# SCR.net
KiCad netlist of a schematic drawn in Altium Designer
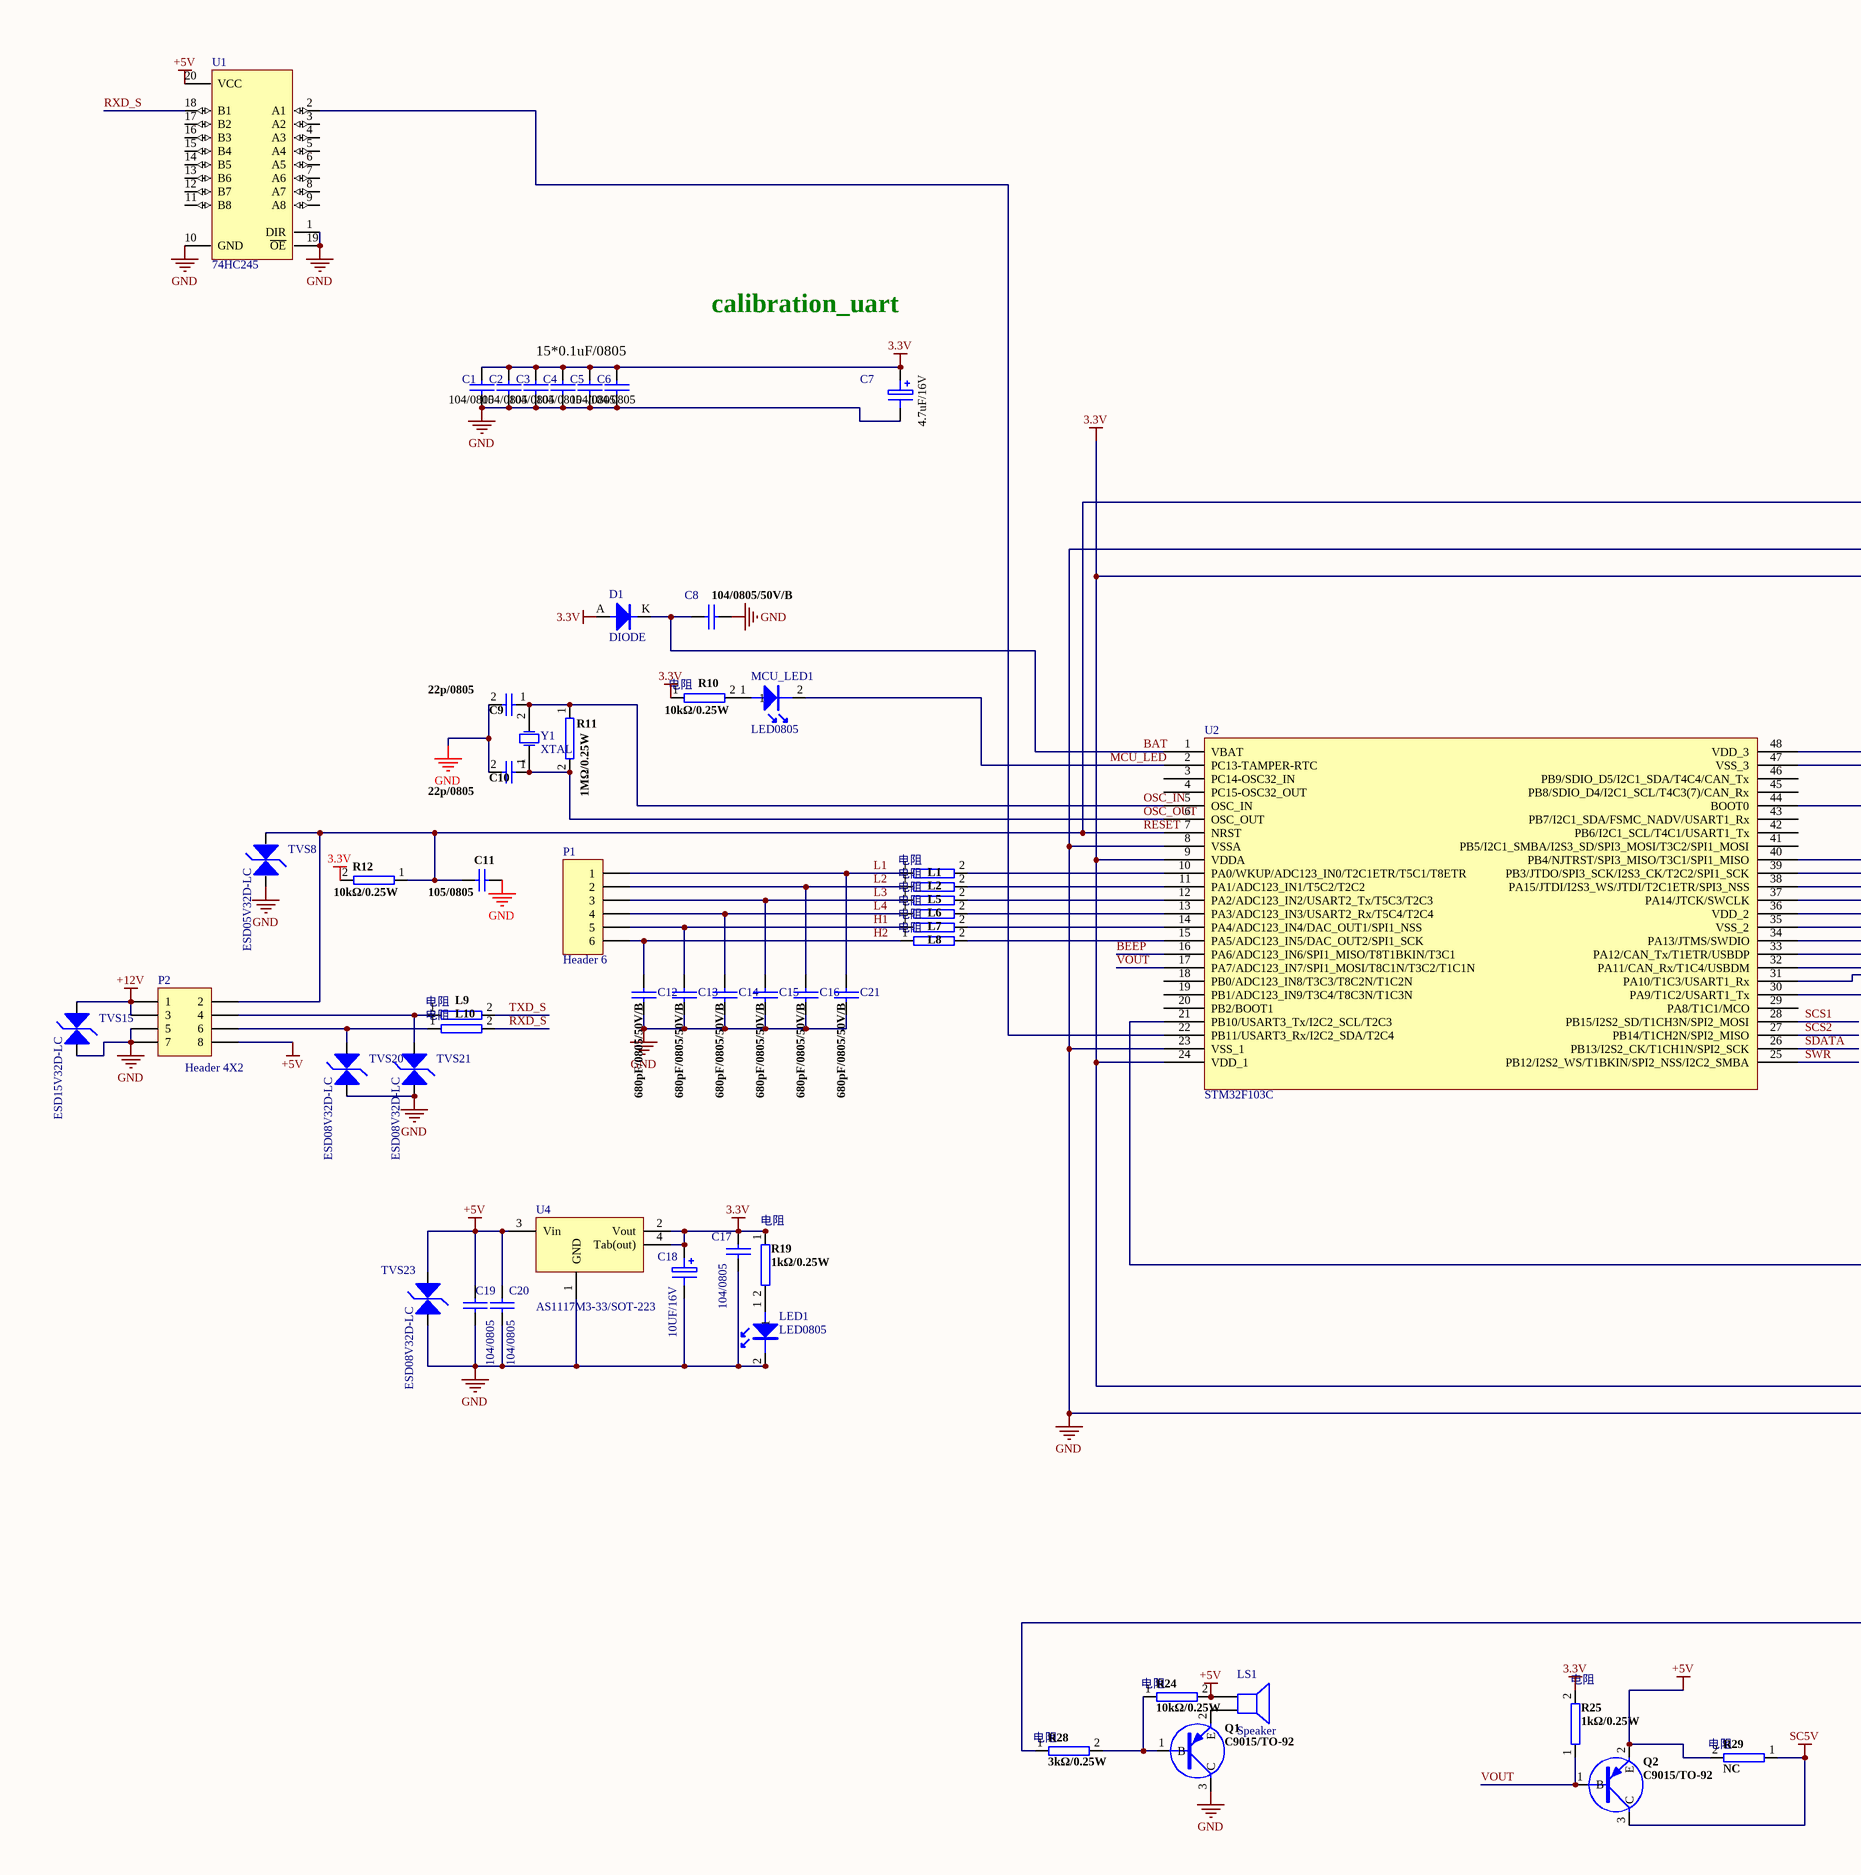
[diagram p0: SCR.SchDoc, left]
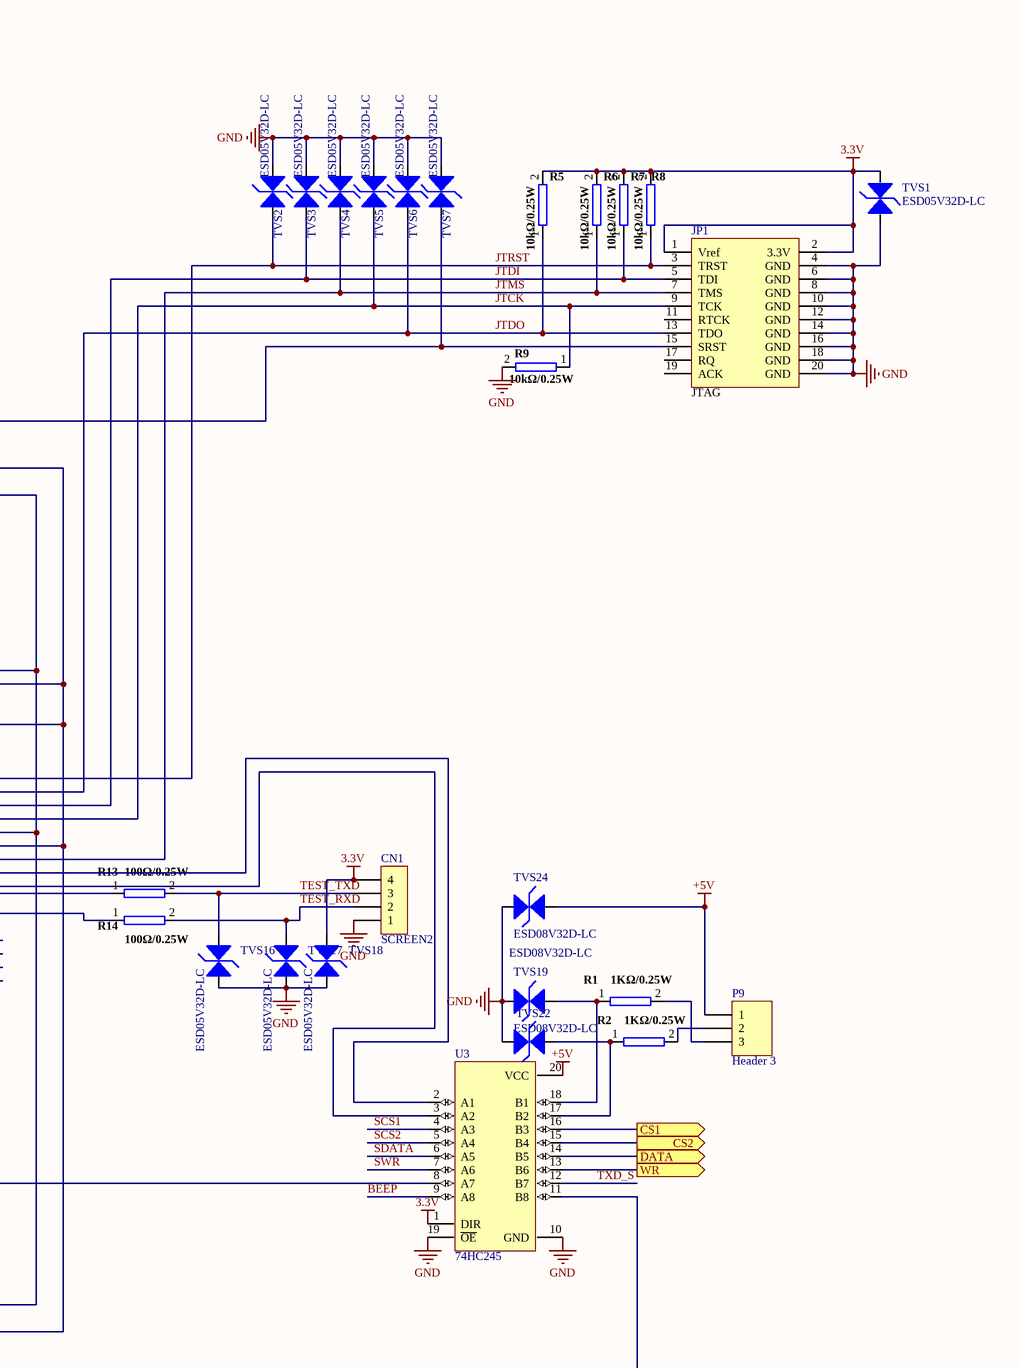
[diagram p1: SCR.SchDoc, right]

(export (version "E")
  (design (tool "Eeschema 10.0.6"))
  (components
    (comp (ref "C1")
      (value "104/0805")
      (footprint "COOLCONTROL:C0805")
      (description "Capacitor")
      (libsource (lib "*") (part "CAP"))
    )
    (comp (ref "C2")
      (value "104/0805")
      (footprint "C0805")
      (description "Capacitor")
      (libsource (lib "*") (part "CAP"))
    )
    (comp (ref "C3")
      (value "104/0805")
      (footprint "C0805")
      (description "Capacitor")
      (libsource (lib "*") (part "CAP"))
    )
    (comp (ref "C4")
      (value "104/0805")
      (footprint "C0805")
      (description "Capacitor")
      (libsource (lib "*") (part "CAP"))
    )
    (comp (ref "C5")
      (value "104/0805")
      (footprint "C0805")
      (description "Capacitor")
      (libsource (lib "*") (part "CAP"))
    )
    (comp (ref "C6")
      (value "104/0805")
      (footprint "C0805")
      (description "Capacitor")
      (libsource (lib "*") (part "CAP"))
    )
    (comp (ref "C7")
      (value "4.7uF/16V")
      (footprint "CAP5X5")
      (description "Electrolytic Capacitor")
      (libsource (lib "*") (part "ELECTRO1"))
    )
    (comp (ref "C8")
      (value "104/0805/50V/B")
      (footprint "C0805")
      (description "Capacitor")
      (fields (field (name "Comment") "104/0805"))
      (libsource (lib "*") (part "CAP"))
    )
    (comp (ref "C9") (value "22p/0805") (footprint "C0805") (libsource (lib "") (part "CAP_2")))
    (comp (ref "C10") (value "22p/0805") (footprint "C0805") (libsource (lib "") (part "CAP_2")))
    (comp (ref "C11")
      (value "105/0805")
      (footprint "C0805")
      (description "Capacitor")
      (fields (field (name "PUBLISHER") "Altium Limited"))
      (libsource (lib "") (part "CAP_1"))
    )
    (comp (ref "C12")
      (value "680pF/0805/50V/B")
      (footprint "C0805")
      (description "Capacitor")
      (fields (field (name "Comment") "104/0805"))
      (libsource (lib "*") (part "CAP"))
    )
    (comp (ref "C13")
      (value "680pF/0805/50V/B")
      (footprint "C0805")
      (description "Capacitor")
      (fields (field (name "Comment") "104/0805"))
      (libsource (lib "*") (part "CAP"))
    )
    (comp (ref "C14")
      (value "680pF/0805/50V/B")
      (footprint "C0805")
      (description "Capacitor")
      (fields (field (name "Comment") "104/0805"))
      (libsource (lib "*") (part "CAP"))
    )
    (comp (ref "C15")
      (value "680pF/0805/50V/B")
      (footprint "C0805")
      (description "Capacitor")
      (fields (field (name "Comment") "104/0805"))
      (libsource (lib "*") (part "CAP"))
    )
    (comp (ref "C16")
      (value "680pF/0805/50V/B")
      (footprint "C0805")
      (description "Capacitor")
      (fields (field (name "Comment") "104/0805"))
      (libsource (lib "*") (part "CAP"))
    )
    (comp (ref "C17")
      (value "104/0805")
      (footprint "C0805")
      (description "Capacitor")
      (libsource (lib "*") (part "CAP"))
    )
    (comp (ref "C18")
      (value "10UF/16V")
      (footprint "C3216")
      (description "Electrolytic Capacitor")
      (libsource (lib "*") (part "ELECTRO1"))
    )
    (comp (ref "C19")
      (value "104/0805")
      (footprint "C0805")
      (description "Capacitor")
      (libsource (lib "*") (part "CAP"))
    )
    (comp (ref "C20")
      (value "104/0805")
      (footprint "C0805")
      (description "Capacitor")
      (libsource (lib "*") (part "CAP"))
    )
    (comp (ref "C21")
      (value "680pF/0805/50V/B")
      (footprint "C0805")
      (description "Capacitor")
      (fields (field (name "Comment") "104/0805"))
      (libsource (lib "*") (part "CAP"))
    )
    (comp (ref "CN1")
      (value "SCREEN2")
      (footprint "COOLCONTROL:4Pin-2.54")
      (description "Connector")
      (libsource (lib "COOLCONTROL") (part "CON4"))
    )
    (comp (ref "D1") (value "DIODE") (footprint "SOD123") (libsource (lib "COOLCONTROL") (part "DIODE")))
    (comp (ref "JP1") (value "JTAG") (footprint "IDC20_A") (libsource (lib "COOLCONTROL") (part "JTAG20")))
    (comp (ref "L1") (value "FBMA-11-160808-601T") (footprint "R0805") (libsource (lib "*") (part "RES2")))
    (comp (ref "L2") (value "FBMA-11-160808-601T") (footprint "R0805") (libsource (lib "*") (part "RES2")))
    (comp (ref "L5") (value "FBMA-11-160808-601T") (footprint "R0805") (libsource (lib "*") (part "RES2")))
    (comp (ref "L6") (value "FBMA-11-160808-601T") (footprint "R0805") (libsource (lib "*") (part "RES2")))
    (comp (ref "L7") (value "FBMA-11-160808-601T") (footprint "R0805") (libsource (lib "*") (part "RES2")))
    (comp (ref "L8") (value "FBMA-11-160808-601T") (footprint "R0805") (libsource (lib "*") (part "RES2")))
    (comp (ref "L9") (value "FBMA-11-160808-601T") (footprint "R0805") (libsource (lib "*") (part "RES2")))
    (comp (ref "L10") (value "FBMA-11-160808-601T") (footprint "R0805") (libsource (lib "*") (part "RES2")))
    (comp (ref "LED1")
      (value "LED0805")
      (footprint "LED_0805")
      (libsource (lib "COOLCONTROL") (part "LED0805"))
    )
    (comp (ref "LS1")
      (value "Speaker")
      (footprint "Thermometer:SPK")
      (description "Loudspeaker")
      (fields (field (name "PUBLISHER") "Altium Limited"))
      (libsource (lib "Miscellaneous Devices") (part "Speaker"))
    )
    (comp (ref "MCU_LED1")
      (value "LED0805")
      (footprint "LED_0805")
      (libsource (lib "COOLCONTROL") (part "LED0805"))
    )
    (comp (ref "P1")
      (value "Header 6")
      (footprint "HDR1X6")
      (description "Header, 6-Pin")
      (fields (field (name "PUBLISHER") "Altium Limited"))
      (libsource (lib "Miscellaneous Connectors") (part "Header 6"))
    )
    (comp (ref "P2")
      (value "Header 4X2")
      (footprint "pcb2D3D库0903:RJ45")
      (description "Header, 4-Pin, Dual row")
      (fields (field (name "PUBLISHER") "Altium Limited"))
      (libsource (lib "Miscellaneous Connectors") (part "Header 4X2"))
    )
    (comp (ref "P9")
      (value "Header 3")
      (footprint "HDR1X3")
      (description "Header, 3-Pin")
      (fields (field (name "PUBLISHER") "Altium Limited"))
      (libsource (lib "Miscellaneous Connectors") (part "Header 3"))
    )
    (comp (ref "Q1") (value "C9015/TO-92") (footprint "TO-92B") (libsource (lib "SCREEN") (part "PNP")))
    (comp (ref "Q2")
      (value "C9015/TO-92")
      (footprint "SOT-23 - 9015")
      (libsource (lib "SCREEN") (part "PNP"))
    )
    (comp (ref "R1") (value "1KΩ/0.25W") (footprint "COOLCONTROL:R0805") (libsource (lib "*") (part "RES2")))
    (comp (ref "R2") (value "1KΩ/0.25W") (footprint "COOLCONTROL:R0805") (libsource (lib "*") (part "RES2")))
    (comp (ref "R5") (value "10kΩ/0.25W") (footprint "R0805") (libsource (lib "") (part "RES2_1")))
    (comp (ref "R6") (value "10kΩ/0.25W") (footprint "R0805") (libsource (lib "") (part "RES2_1")))
    (comp (ref "R7") (value "10kΩ/0.25W") (footprint "R0805") (libsource (lib "") (part "RES2_1")))
    (comp (ref "R8") (value "10kΩ/0.25W") (footprint "R0805") (libsource (lib "") (part "RES2_1")))
    (comp (ref "R9") (value "10kΩ/0.25W") (footprint "R0805") (libsource (lib "") (part "RES2_1")))
    (comp (ref "R10") (value "10kΩ/0.25W") (footprint "R0805") (libsource (lib "*") (part "RES2")))
    (comp (ref "R11") (value "1MΩ/0.25W") (footprint "R0805") (libsource (lib "*") (part "RES2")))
    (comp (ref "R12") (value "10kΩ/0.25W") (footprint "R0805") (libsource (lib "*") (part "RES2")))
    (comp (ref "R13")
      (value "100Ω/0.25W")
      (footprint "COOLCONTROL:R0805")
      (libsource (lib "*") (part "RES2"))
    )
    (comp (ref "R14")
      (value "100Ω/0.25W")
      (footprint "COOLCONTROL:R0805")
      (libsource (lib "*") (part "RES2"))
    )
    (comp (ref "R19") (value "1kΩ/0.25W") (footprint "R0805") (libsource (lib "*") (part "RES2")))
    (comp (ref "R24") (value "10kΩ/0.25W") (footprint "R0805") (libsource (lib "*") (part "RES2")))
    (comp (ref "R25") (value "1kΩ/0.25W") (footprint "R0805") (libsource (lib "*") (part "RES2")))
    (comp (ref "R28") (value "3kΩ/0.25W") (footprint "R0805") (libsource (lib "*") (part "RES2")))
    (comp (ref "R29") (value "NC") (footprint "R0805") (libsource (lib "*") (part "RES2")))
    (comp (ref "TVS1")
      (value "ESD05V32D-LC")
      (footprint "SOD323")
      (libsource (lib "COOLCONTROL") (part "TVS"))
    )
    (comp (ref "TVS2")
      (value "ESD05V32D-LC")
      (footprint "SOD323")
      (libsource (lib "COOLCONTROL") (part "TVS"))
    )
    (comp (ref "TVS3")
      (value "ESD05V32D-LC")
      (footprint "SOD323")
      (libsource (lib "COOLCONTROL") (part "TVS"))
    )
    (comp (ref "TVS4")
      (value "ESD05V32D-LC")
      (footprint "SOD323")
      (libsource (lib "COOLCONTROL") (part "TVS"))
    )
    (comp (ref "TVS5")
      (value "ESD05V32D-LC")
      (footprint "SOD323")
      (libsource (lib "COOLCONTROL") (part "TVS"))
    )
    (comp (ref "TVS6")
      (value "ESD05V32D-LC")
      (footprint "SOD323")
      (libsource (lib "COOLCONTROL") (part "TVS"))
    )
    (comp (ref "TVS7")
      (value "ESD05V32D-LC")
      (footprint "SOD323")
      (libsource (lib "COOLCONTROL") (part "TVS"))
    )
    (comp (ref "TVS8")
      (value "ESD05V32D-LC")
      (footprint "SOD323")
      (libsource (lib "COOLCONTROL") (part "TVS"))
    )
    (comp (ref "TVS15")
      (value "ESD15V32D-LC")
      (footprint "SOD323")
      (libsource (lib "COOLCONTROL") (part "TVS"))
    )
    (comp (ref "TVS16")
      (value "ESD05V32D-LC")
      (footprint "SOD323")
      (libsource (lib "COOLCONTROL") (part "TVS"))
    )
    (comp (ref "TVS17")
      (value "ESD05V32D-LC")
      (footprint "SOD323")
      (libsource (lib "COOLCONTROL") (part "TVS"))
    )
    (comp (ref "TVS18")
      (value "ESD05V32D-LC")
      (footprint "SOD323")
      (libsource (lib "COOLCONTROL") (part "TVS"))
    )
    (comp (ref "TVS19")
      (value "ESD08V32D-LC")
      (footprint "SOD323")
      (libsource (lib "COOLCONTROL") (part "TVS"))
    )
    (comp (ref "TVS20")
      (value "ESD08V32D-LC")
      (footprint "SOD323")
      (libsource (lib "COOLCONTROL") (part "TVS"))
    )
    (comp (ref "TVS21")
      (value "ESD08V32D-LC")
      (footprint "SOD323")
      (libsource (lib "COOLCONTROL") (part "TVS"))
    )
    (comp (ref "TVS22")
      (value "ESD08V32D-LC")
      (footprint "SOD323")
      (libsource (lib "COOLCONTROL") (part "TVS"))
    )
    (comp (ref "TVS23")
      (value "ESD08V32D-LC")
      (footprint "SOD323")
      (libsource (lib "COOLCONTROL") (part "TVS"))
    )
    (comp (ref "TVS24")
      (value "ESD08V32D-LC")
      (footprint "SOD323")
      (libsource (lib "COOLCONTROL") (part "TVS"))
    )
    (comp (ref "U1")
      (value "74HC245")
      (footprint "JD1622(V3.0):SOP-20")
      (libsource (lib "") (part "74LS245_1"))
    )
    (comp (ref "U2")
      (value "STM32F103C")
      (footprint "Thermometer:LC-LQFP-48_7x7x05P")
      (description "STM32单片机48引脚")
      (libsource (lib "Thermometer") (part "STM32F103C"))
    )
    (comp (ref "U3")
      (value "74HC245")
      (footprint "JD1622(V3.0):SOP-20")
      (libsource (lib "制冷控制") (part "74LS245"))
    )
    (comp (ref "U4")
      (value "AS1117M3-33/SOT-223")
      (footprint "Thermometer:SOT-223-3L(M3)")
      (libsource (lib "COOLCONTROL") (part "AS1117M3-33"))
    )
    (comp (ref "Y1")
      (value "XTAL")
      (footprint "JD1622(V3.0):XTAL2")
      (description "Crystal Oscillator")
      (fields (field (name "PUBLISHER") "Altium Limited"))
      (libsource (lib "Miscellaneous Devices") (part "XTAL"))
    )
  )
  (nets
    (net (code "1") (name "+5V") (class "Default")
      (node (ref "C19") (pin "1") (pinfunction "1_1") (pintype "passive"))
      (node (ref "C20") (pin "1") (pinfunction "1_1") (pintype "passive"))
      (node (ref "LS1") (pin "1") (pinfunction "1_1") (pintype "passive"))
      (node (ref "P2") (pin "8") (pinfunction "8_8") (pintype "passive"))
      (node (ref "P9") (pin "1") (pinfunction "1_1") (pintype "passive"))
      (node (ref "Q2") (pin "2") (pinfunction "E_2") (pintype "passive"))
      (node (ref "R24") (pin "2") (pintype "passive"))
      (node (ref "R29") (pin "2") (pintype "passive"))
      (node (ref "TVS23") (pin "1") (pinfunction "1_1") (pintype "passive"))
      (node (ref "TVS24") (pin "1") (pinfunction "1_1") (pintype "passive"))
      (node (ref "U1") (pin "20") (pinfunction "VCC_20") (pintype "power_in"))
      (node (ref "U3") (pin "20") (pinfunction "VCC_20") (pintype "power_in"))
      (node (ref "U4") (pin "3") (pinfunction "Vin_3") (pintype "passive"))
    )
    (net (code "2") (name "+12V") (class "Default")
      (node (ref "P2") (pin "1") (pinfunction "1_1") (pintype "passive"))
      (node (ref "P2") (pin "3") (pinfunction "3_3") (pintype "passive"))
      (node (ref "TVS15") (pin "1") (pinfunction "1_1") (pintype "passive"))
    )
    (net (code "3") (name "/BAT") (class "Default")
      (node (ref "C8") (pin "1") (pinfunction "1_1") (pintype "passive"))
      (node (ref "D1") (pin "K") (pinfunction "K_K") (pintype "passive"))
      (node (ref "U2") (pin "1") (pinfunction "VBAT_1") (pintype "passive"))
    )
    (net (code "4") (name "/BEEP") (class "Default")
      (node (ref "U2") (pin "16") (pinfunction "PA6/ADC123_IN6/SPI1_MISO/T8T1BKIN/T3C1_16") (pintype "passive"))
      (node (ref "U3") (pin "9") (pinfunction "A8_9") (pintype "bidirectional"))
    )
    (net (code "5") (name "/CS1") (class "Default")
      (node (ref "U3") (pin "16") (pinfunction "B3_16") (pintype "bidirectional"))
    )
    (net (code "6") (name "/CS2") (class "Default")
      (node (ref "U3") (pin "15") (pinfunction "B4_15") (pintype "bidirectional"))
    )
    (net (code "7") (name "/DATA") (class "Default")
      (node (ref "U3") (pin "14") (pinfunction "B5_14") (pintype "bidirectional"))
    )
    (net (code "8") (name "/H1") (class "Default")
      (node (ref "C13") (pin "2") (pinfunction "2_2") (pintype "passive"))
      (node (ref "L7") (pin "1") (pintype "passive"))
      (node (ref "P1") (pin "5") (pinfunction "5_5") (pintype "passive"))
    )
    (net (code "9") (name "/H2") (class "Default")
      (node (ref "C12") (pin "2") (pinfunction "2_2") (pintype "passive"))
      (node (ref "L8") (pin "1") (pintype "passive"))
      (node (ref "P1") (pin "6") (pinfunction "6_6") (pintype "passive"))
    )
    (net (code "10") (name "/JTCK") (class "Default")
      (node (ref "JP1") (pin "9") (pinfunction "TCK_9") (pintype "passive"))
      (node (ref "R9") (pin "1") (pintype "passive"))
      (node (ref "TVS5") (pin "1") (pinfunction "1_1") (pintype "passive"))
      (node (ref "U2") (pin "37") (pinfunction "PA14/JTCK/SWCLK_37") (pintype "passive"))
    )
    (net (code "11") (name "/JTDI") (class "Default")
      (node (ref "JP1") (pin "5") (pinfunction "TDI_5") (pintype "passive"))
      (node (ref "R7") (pin "1") (pintype "passive"))
      (node (ref "TVS3") (pin "1") (pinfunction "1_1") (pintype "passive"))
      (node (ref "U2") (pin "38") (pinfunction "PA15/JTDI/I2S3_WS/JTDI/T2C1ETR/SPI3_NSS_38") (pintype "passive"))
    )
    (net (code "12") (name "/JTDO") (class "Default")
      (node (ref "JP1") (pin "13") (pinfunction "TDO_13") (pintype "passive"))
      (node (ref "R5") (pin "1") (pintype "passive"))
      (node (ref "TVS6") (pin "1") (pinfunction "1_1") (pintype "passive"))
      (node (ref "U2") (pin "39") (pinfunction "PB3/JTDO/SPI3_SCK/I2S3_CK/T2C2/SPI1_SCK_39") (pintype "passive"))
    )
    (net (code "13") (name "/JTMS") (class "Default")
      (node (ref "JP1") (pin "7") (pinfunction "TMS_7") (pintype "passive"))
      (node (ref "R6") (pin "1") (pintype "passive"))
      (node (ref "TVS4") (pin "1") (pinfunction "1_1") (pintype "passive"))
      (node (ref "U2") (pin "34") (pinfunction "PA13/JTMS/SWDIO_34") (pintype "passive"))
    )
    (net (code "14") (name "/JTRST") (class "Default")
      (node (ref "JP1") (pin "3") (pinfunction "TRST_3") (pintype "passive"))
      (node (ref "R8") (pin "1") (pintype "passive"))
      (node (ref "TVS2") (pin "1") (pinfunction "1_1") (pintype "passive"))
      (node (ref "U2") (pin "40") (pinfunction "PB4/NJTRST/SPI3_MISO/T3C1/SPI1_MISO_40") (pintype "passive"))
    )
    (net (code "15") (name "/L1") (class "Default")
      (node (ref "C21") (pin "2") (pinfunction "2_2") (pintype "passive"))
      (node (ref "L1") (pin "1") (pintype "passive"))
      (node (ref "P1") (pin "1") (pinfunction "1_1") (pintype "passive"))
    )
    (net (code "16") (name "/L2") (class "Default")
      (node (ref "C16") (pin "2") (pinfunction "2_2") (pintype "passive"))
      (node (ref "L2") (pin "1") (pintype "passive"))
      (node (ref "P1") (pin "2") (pinfunction "2_2") (pintype "passive"))
    )
    (net (code "17") (name "/L3") (class "Default")
      (node (ref "C15") (pin "2") (pinfunction "2_2") (pintype "passive"))
      (node (ref "L5") (pin "1") (pintype "passive"))
      (node (ref "P1") (pin "3") (pinfunction "3_3") (pintype "passive"))
    )
    (net (code "18") (name "/L4") (class "Default")
      (node (ref "C14") (pin "2") (pinfunction "2_2") (pintype "passive"))
      (node (ref "L6") (pin "1") (pintype "passive"))
      (node (ref "P1") (pin "4") (pinfunction "4_4") (pintype "passive"))
    )
    (net (code "19") (name "/MCU_LED") (class "Default")
      (node (ref "MCU_LED1") (pin "2") (pinfunction "2_2") (pintype "passive"))
      (node (ref "U2") (pin "2") (pinfunction "PC13-TAMPER-RTC_2") (pintype "passive"))
    )
    (net (code "20") (name "/OSC_IN") (class "Default")
      (node (ref "C9") (pin "1") (pintype "passive"))
      (node (ref "R11") (pin "1") (pintype "passive"))
      (node (ref "U2") (pin "5") (pinfunction "OSC_IN_5") (pintype "passive"))
      (node (ref "Y1") (pin "2") (pinfunction "OSC2_2") (pintype "passive"))
    )
    (net (code "21") (name "/OSC_OUT") (class "Default")
      (node (ref "C10") (pin "1") (pintype "passive"))
      (node (ref "R11") (pin "2") (pintype "passive"))
      (node (ref "U2") (pin "6") (pinfunction "OSC_OUT_6") (pintype "passive"))
      (node (ref "Y1") (pin "1") (pinfunction "OSC1_1") (pintype "passive"))
    )
    (net (code "22") (name "/RESET") (class "Default")
      (node (ref "C11") (pin "2") (pinfunction "2_2") (pintype "passive"))
      (node (ref "JP1") (pin "15") (pinfunction "SRST_15") (pintype "passive"))
      (node (ref "P2") (pin "2") (pinfunction "2_2") (pintype "passive"))
      (node (ref "R12") (pin "1") (pintype "passive"))
      (node (ref "TVS7") (pin "1") (pinfunction "1_1") (pintype "passive"))
      (node (ref "TVS8") (pin "1") (pinfunction "1_1") (pintype "passive"))
      (node (ref "U2") (pin "7") (pinfunction "NRST_7") (pintype "passive"))
    )
    (net (code "23") (name "/RXD_S") (class "Default")
      (node (ref "L10") (pin "2") (pintype "passive"))
      (node (ref "U1") (pin "18") (pinfunction "B1_18") (pintype "bidirectional"))
    )
    (net (code "24") (name "/SCS1") (class "Default")
      (node (ref "U2") (pin "28") (pinfunction "PB15/I2S2_SD/T1CH3N/SPI2_MOSI_28") (pintype "passive"))
      (node (ref "U3") (pin "4") (pinfunction "A3_4") (pintype "bidirectional"))
    )
    (net (code "25") (name "/SCS2") (class "Default")
      (node (ref "U2") (pin "27") (pinfunction "PB14/T1CH2N/SPI2_MISO_27") (pintype "passive"))
      (node (ref "U3") (pin "5") (pinfunction "A4_5") (pintype "bidirectional"))
    )
    (net (code "26") (name "/SDATA") (class "Default")
      (node (ref "U2") (pin "26") (pinfunction "PB13/I2S2_CK/T1CH1N/SPI2_SCK_26") (pintype "passive"))
      (node (ref "U3") (pin "6") (pinfunction "A5_6") (pintype "bidirectional"))
    )
    (net (code "27") (name "/SWR") (class "Default")
      (node (ref "U2") (pin "25") (pinfunction "PB12/I2S2_WS/T1BKIN/SPI2_NSS/I2C2_SMBA_25") (pintype "passive"))
      (node (ref "U3") (pin "7") (pinfunction "A6_7") (pintype "bidirectional"))
    )
    (net (code "28") (name "/TEST_RXD") (class "Default")
      (node (ref "CN1") (pin "2") (pinfunction "2_2") (pintype "passive"))
      (node (ref "R14") (pin "2") (pintype "passive"))
      (node (ref "TVS17") (pin "1") (pinfunction "1_1") (pintype "passive"))
    )
    (net (code "29") (name "/TEST_TXD") (class "Default")
      (node (ref "CN1") (pin "3") (pinfunction "3_3") (pintype "passive"))
      (node (ref "R13") (pin "2") (pintype "passive"))
      (node (ref "TVS16") (pin "1") (pinfunction "1_1") (pintype "passive"))
    )
    (net (code "30") (name "/TXD_S") (class "Default")
      (node (ref "L9") (pin "2") (pintype "passive"))
      (node (ref "U3") (pin "12") (pinfunction "B7_12") (pintype "bidirectional"))
    )
    (net (code "31") (name "/VOUT") (class "Default")
      (node (ref "Q2") (pin "1") (pinfunction "B_1") (pintype "passive"))
      (node (ref "R25") (pin "1") (pintype "passive"))
      (node (ref "U2") (pin "17") (pinfunction "PA7/ADC123_IN7/SPI1_MOSI/T8C1N/T3C2/T1C1N_17") (pintype "passive"))
    )
    (net (code "32") (name "/WR") (class "Default")
      (node (ref "U3") (pin "13") (pinfunction "B6_13") (pintype "bidirectional"))
    )
    (net (code "33") (name "3.3V") (class "Default")
      (node (ref "C1") (pin "1") (pinfunction "1_1") (pintype "passive"))
      (node (ref "C17") (pin "1") (pinfunction "1_1") (pintype "passive"))
      (node (ref "C18") (pin "1") (pinfunction "1_1") (pintype "passive"))
      (node (ref "C2") (pin "1") (pinfunction "1_1") (pintype "passive"))
      (node (ref "C3") (pin "1") (pinfunction "1_1") (pintype "passive"))
      (node (ref "C4") (pin "1") (pinfunction "1_1") (pintype "passive"))
      (node (ref "C5") (pin "1") (pinfunction "1_1") (pintype "passive"))
      (node (ref "C6") (pin "1") (pinfunction "1_1") (pintype "passive"))
      (node (ref "C7") (pin "1") (pinfunction "1_1") (pintype "passive"))
      (node (ref "CN1") (pin "4") (pinfunction "4_4") (pintype "passive"))
      (node (ref "D1") (pin "A") (pinfunction "A_A") (pintype "passive"))
      (node (ref "JP1") (pin "1") (pinfunction "Vref_1") (pintype "passive"))
      (node (ref "JP1") (pin "2") (pinfunction "3.3V_2") (pintype "passive"))
      (node (ref "R10") (pin "1") (pintype "passive"))
      (node (ref "R12") (pin "2") (pintype "passive"))
      (node (ref "R19") (pin "1") (pintype "passive"))
      (node (ref "R25") (pin "2") (pintype "passive"))
      (node (ref "R5") (pin "2") (pintype "passive"))
      (node (ref "R6") (pin "2") (pintype "passive"))
      (node (ref "R7") (pin "2") (pintype "passive"))
      (node (ref "R8") (pin "2") (pintype "passive"))
      (node (ref "TVS1") (pin "1") (pinfunction "1_1") (pintype "passive"))
      (node (ref "TVS18") (pin "1") (pinfunction "1_1") (pintype "passive"))
      (node (ref "U2") (pin "24") (pinfunction "VDD_1_24") (pintype "passive"))
      (node (ref "U2") (pin "36") (pinfunction "VDD_2_36") (pintype "passive"))
      (node (ref "U2") (pin "48") (pinfunction "VDD_3_48") (pintype "passive"))
      (node (ref "U2") (pin "9") (pinfunction "VDDA_9") (pintype "passive"))
      (node (ref "U3") (pin "1") (pinfunction "DIR_1") (pintype "passive"))
      (node (ref "U4") (pin "2") (pinfunction "Vout_2") (pintype "passive"))
      (node (ref "U4") (pin "4") (pinfunction "Tab(out)_4") (pintype "passive"))
    )
    (net (code "34") (name "GND") (class "Default")
      (node (ref "C1") (pin "2") (pinfunction "2_2") (pintype "passive"))
      (node (ref "C10") (pin "2") (pintype "passive"))
      (node (ref "C11") (pin "1") (pinfunction "1_1") (pintype "passive"))
      (node (ref "C12") (pin "1") (pinfunction "1_1") (pintype "passive"))
      (node (ref "C13") (pin "1") (pinfunction "1_1") (pintype "passive"))
      (node (ref "C14") (pin "1") (pinfunction "1_1") (pintype "passive"))
      (node (ref "C15") (pin "1") (pinfunction "1_1") (pintype "passive"))
      (node (ref "C16") (pin "1") (pinfunction "1_1") (pintype "passive"))
      (node (ref "C17") (pin "2") (pinfunction "2_2") (pintype "passive"))
      (node (ref "C18") (pin "2") (pinfunction "2_2") (pintype "passive"))
      (node (ref "C19") (pin "2") (pinfunction "2_2") (pintype "passive"))
      (node (ref "C2") (pin "2") (pinfunction "2_2") (pintype "passive"))
      (node (ref "C20") (pin "2") (pinfunction "2_2") (pintype "passive"))
      (node (ref "C21") (pin "1") (pinfunction "1_1") (pintype "passive"))
      (node (ref "C3") (pin "2") (pinfunction "2_2") (pintype "passive"))
      (node (ref "C4") (pin "2") (pinfunction "2_2") (pintype "passive"))
      (node (ref "C5") (pin "2") (pinfunction "2_2") (pintype "passive"))
      (node (ref "C6") (pin "2") (pinfunction "2_2") (pintype "passive"))
      (node (ref "C7") (pin "2") (pinfunction "2_2") (pintype "passive"))
      (node (ref "C8") (pin "2") (pinfunction "2_2") (pintype "passive"))
      (node (ref "C9") (pin "2") (pintype "passive"))
      (node (ref "CN1") (pin "1") (pinfunction "1_1") (pintype "passive"))
      (node (ref "JP1") (pin "10") (pinfunction "GND_10") (pintype "passive"))
      (node (ref "JP1") (pin "12") (pinfunction "GND_12") (pintype "passive"))
      (node (ref "JP1") (pin "14") (pinfunction "GND_14") (pintype "passive"))
      (node (ref "JP1") (pin "16") (pinfunction "GND_16") (pintype "passive"))
      (node (ref "JP1") (pin "18") (pinfunction "GND_18") (pintype "passive"))
      (node (ref "JP1") (pin "20") (pinfunction "GND_20") (pintype "passive"))
      (node (ref "JP1") (pin "4") (pinfunction "GND_4") (pintype "passive"))
      (node (ref "JP1") (pin "6") (pinfunction "GND_6") (pintype "passive"))
      (node (ref "JP1") (pin "8") (pinfunction "GND_8") (pintype "passive"))
      (node (ref "LED1") (pin "2") (pinfunction "2_2") (pintype "passive"))
      (node (ref "P2") (pin "5") (pinfunction "5_5") (pintype "passive"))
      (node (ref "P2") (pin "7") (pinfunction "7_7") (pintype "passive"))
      (node (ref "Q1") (pin "3") (pinfunction "C_3") (pintype "passive"))
      (node (ref "R9") (pin "2") (pintype "passive"))
      (node (ref "TVS1") (pin "2") (pinfunction "2_2") (pintype "passive"))
      (node (ref "TVS15") (pin "2") (pinfunction "2_2") (pintype "passive"))
      (node (ref "TVS16") (pin "2") (pinfunction "2_2") (pintype "passive"))
      (node (ref "TVS17") (pin "2") (pinfunction "2_2") (pintype "passive"))
      (node (ref "TVS18") (pin "2") (pinfunction "2_2") (pintype "passive"))
      (node (ref "TVS19") (pin "2") (pinfunction "2_2") (pintype "passive"))
      (node (ref "TVS2") (pin "2") (pinfunction "2_2") (pintype "passive"))
      (node (ref "TVS20") (pin "2") (pinfunction "2_2") (pintype "passive"))
      (node (ref "TVS21") (pin "2") (pinfunction "2_2") (pintype "passive"))
      (node (ref "TVS22") (pin "1") (pinfunction "1_1") (pintype "passive"))
      (node (ref "TVS23") (pin "2") (pinfunction "2_2") (pintype "passive"))
      (node (ref "TVS24") (pin "2") (pinfunction "2_2") (pintype "passive"))
      (node (ref "TVS3") (pin "2") (pinfunction "2_2") (pintype "passive"))
      (node (ref "TVS4") (pin "2") (pinfunction "2_2") (pintype "passive"))
      (node (ref "TVS5") (pin "2") (pinfunction "2_2") (pintype "passive"))
      (node (ref "TVS6") (pin "2") (pinfunction "2_2") (pintype "passive"))
      (node (ref "TVS7") (pin "2") (pinfunction "2_2") (pintype "passive"))
      (node (ref "TVS8") (pin "2") (pinfunction "2_2") (pintype "passive"))
      (node (ref "U1") (pin "1") (pinfunction "DIR_1") (pintype "passive"))
      (node (ref "U1") (pin "10") (pinfunction "GND_10") (pintype "passive"))
      (node (ref "U1") (pin "19") (pinfunction "OE_19") (pintype "passive"))
      (node (ref "U2") (pin "23") (pinfunction "VSS_1_23") (pintype "passive"))
      (node (ref "U2") (pin "35") (pinfunction "VSS_2_35") (pintype "passive"))
      (node (ref "U2") (pin "44") (pinfunction "BOOT0_44") (pintype "passive"))
      (node (ref "U2") (pin "47") (pinfunction "VSS_3_47") (pintype "passive"))
      (node (ref "U2") (pin "8") (pinfunction "VSSA_8") (pintype "passive"))
      (node (ref "U3") (pin "10") (pinfunction "GND_10") (pintype "passive"))
      (node (ref "U3") (pin "19") (pinfunction "OE_19") (pintype "passive"))
      (node (ref "U4") (pin "1") (pinfunction "GND_1") (pintype "passive"))
    )
    (net (code "35") (name "Net-(L9-Pad1)") (class "Default")
      (node (ref "L9") (pin "1") (pintype "passive"))
      (node (ref "P2") (pin "4") (pinfunction "4_4") (pintype "passive"))
      (node (ref "TVS21") (pin "1") (pinfunction "1_1") (pintype "passive"))
    )
    (net (code "36") (name "Net-(L10-Pad1)") (class "Default")
      (node (ref "L10") (pin "1") (pintype "passive"))
      (node (ref "P2") (pin "6") (pinfunction "6_6") (pintype "passive"))
      (node (ref "TVS20") (pin "1") (pinfunction "1_1") (pintype "passive"))
    )
    (net (code "37") (name "Net-(LED1-Pad1)") (class "Default")
      (node (ref "LED1") (pin "1") (pinfunction "1_1") (pintype "passive"))
      (node (ref "R19") (pin "2") (pintype "passive"))
    )
    (net (code "38") (name "Net-(MCU_LED1-Pad1)") (class "Default")
      (node (ref "MCU_LED1") (pin "1") (pinfunction "1_1") (pintype "passive"))
      (node (ref "R10") (pin "2") (pintype "passive"))
    )
    (net (code "39") (name "Net-(P9-Pad2)") (class "Default")
      (node (ref "P9") (pin "2") (pinfunction "2_2") (pintype "passive"))
      (node (ref "R2") (pin "2") (pintype "passive"))
    )
    (net (code "40") (name "Net-(P9-Pad3)") (class "Default")
      (node (ref "P9") (pin "3") (pinfunction "3_3") (pintype "passive"))
      (node (ref "R1") (pin "2") (pintype "passive"))
    )
    (net (code "41") (name "Net-(Q1-B)") (class "Default")
      (node (ref "Q1") (pin "1") (pinfunction "B_1") (pintype "passive"))
      (node (ref "R24") (pin "1") (pintype "passive"))
      (node (ref "R28") (pin "2") (pintype "passive"))
    )
    (net (code "42") (name "Net-(Q1-E)") (class "Default")
      (node (ref "LS1") (pin "2") (pinfunction "2_2") (pintype "passive"))
      (node (ref "Q1") (pin "2") (pinfunction "E_2") (pintype "passive"))
    )
    (net (code "43") (name "Net-(U1-A1)") (class "Default")
      (node (ref "U1") (pin "2") (pinfunction "A1_2") (pintype "bidirectional"))
      (node (ref "U2") (pin "22") (pinfunction "PB11/USART3_Rx/I2C2_SDA/T2C4_22") (pintype "passive"))
    )
    (net (code "44") (name "Net-(U2-PA0{slash}WKUP{slash}ADC123_IN0{slash}T2C1ETR{slash}T5C1{slash}T8ETR)") (class "Default")
      (node (ref "L1") (pin "2") (pintype "passive"))
      (node (ref "U2") (pin "10") (pinfunction "PA0/WKUP/ADC123_IN0/T2C1ETR/T5C1/T8ETR_10") (pintype "passive"))
    )
    (net (code "45") (name "Net-(U2-PA1{slash}ADC123_IN1{slash}T5C2{slash}T2C2)") (class "Default")
      (node (ref "L2") (pin "2") (pintype "passive"))
      (node (ref "U2") (pin "11") (pinfunction "PA1/ADC123_IN1/T5C2/T2C2_11") (pintype "passive"))
    )
    (net (code "46") (name "Net-(U2-PA2{slash}ADC123_IN2{slash}USART2_Tx{slash}T5C3{slash}T2C3)") (class "Default")
      (node (ref "L5") (pin "2") (pintype "passive"))
      (node (ref "U2") (pin "12") (pinfunction "PA2/ADC123_IN2/USART2_Tx/T5C3/T2C3_12") (pintype "passive"))
    )
    (net (code "47") (name "Net-(U2-PA3{slash}ADC123_IN3{slash}USART2_Rx{slash}T5C4{slash}T2C4)") (class "Default")
      (node (ref "L6") (pin "2") (pintype "passive"))
      (node (ref "U2") (pin "13") (pinfunction "PA3/ADC123_IN3/USART2_Rx/T5C4/T2C4_13") (pintype "passive"))
    )
    (net (code "48") (name "Net-(U2-PA4{slash}ADC123_IN4{slash}DAC_OUT1{slash}SPI1_NSS)") (class "Default")
      (node (ref "L7") (pin "2") (pintype "passive"))
      (node (ref "U2") (pin "14") (pinfunction "PA4/ADC123_IN4/DAC_OUT1/SPI1_NSS_14") (pintype "passive"))
    )
    (net (code "49") (name "Net-(U2-PA5{slash}ADC123_IN5{slash}DAC_OUT2{slash}SPI1_SCK)") (class "Default")
      (node (ref "L8") (pin "2") (pintype "passive"))
      (node (ref "U2") (pin "15") (pinfunction "PA5/ADC123_IN5/DAC_OUT2/SPI1_SCK_15") (pintype "passive"))
    )
    (net (code "50") (name "Net-(U2-PA9{slash}T1C2{slash}USART1_Tx)") (class "Default")
      (node (ref "R14") (pin "1") (pintype "passive"))
      (node (ref "U2") (pin "30") (pinfunction "PA9/T1C2/USART1_Tx_30") (pintype "passive"))
    )
    (net (code "51") (name "Net-(U2-PA10{slash}T1C3{slash}USART1_Rx)") (class "Default")
      (node (ref "R13") (pin "1") (pintype "passive"))
      (node (ref "U2") (pin "31") (pinfunction "PA10/T1C3/USART1_Rx_31") (pintype "passive"))
    )
    (net (code "52") (name "Net-(U2-PA11{slash}CAN_Rx{slash}T1C4{slash}USBDM)") (class "Default")
      (node (ref "U2") (pin "32") (pinfunction "PA11/CAN_Rx/T1C4/USBDM_32") (pintype "passive"))
      (node (ref "U3") (pin "3") (pinfunction "A2_3") (pintype "bidirectional"))
    )
    (net (code "53") (name "Net-(U2-PA12{slash}CAN_Tx{slash}T1ETR{slash}USBDP)") (class "Default")
      (node (ref "U2") (pin "33") (pinfunction "PA12/CAN_Tx/T1ETR/USBDP_33") (pintype "passive"))
      (node (ref "U3") (pin "2") (pinfunction "A1_2") (pintype "bidirectional"))
    )
    (net (code "54") (name "Net-(U2-PB10{slash}USART3_Tx{slash}I2C2_SCL{slash}T2C3)") (class "Default")
      (node (ref "U2") (pin "21") (pinfunction "PB10/USART3_Tx/I2C2_SCL/T2C3_21") (pintype "passive"))
      (node (ref "U3") (pin "8") (pinfunction "A7_8") (pintype "bidirectional"))
    )
    (net (code "55") (name "Net-(U3-B1)") (class "Default")
      (node (ref "R1") (pin "1") (pintype "passive"))
      (node (ref "TVS19") (pin "1") (pinfunction "1_1") (pintype "passive"))
      (node (ref "U3") (pin "18") (pinfunction "B1_18") (pintype "bidirectional"))
    )
    (net (code "56") (name "Net-(U3-B2)") (class "Default")
      (node (ref "R2") (pin "1") (pintype "passive"))
      (node (ref "TVS22") (pin "2") (pinfunction "2_2") (pintype "passive"))
      (node (ref "U3") (pin "17") (pinfunction "B2_17") (pintype "bidirectional"))
    )
    (net (code "57") (name "Net-(U3-B8)") (class "Default")
      (node (ref "R28") (pin "1") (pintype "passive"))
      (node (ref "U3") (pin "11") (pinfunction "B8_11") (pintype "bidirectional"))
    )
    (net (code "58") (name "SC5V") (class "Default")
      (node (ref "Q2") (pin "3") (pinfunction "C_3") (pintype "passive"))
      (node (ref "R29") (pin "1") (pintype "passive"))
    )
    (net (code "59") (name "unconnected-(JP1-ACK-Pad19)") (class "Default")
      (node (ref "JP1") (pin "19") (pinfunction "ACK_19") (pintype "passive"))
    )
    (net (code "60") (name "unconnected-(JP1-RQ-Pad17)") (class "Default")
      (node (ref "JP1") (pin "17") (pinfunction "RQ_17") (pintype "passive"))
    )
    (net (code "61") (name "unconnected-(JP1-RTCK-Pad11)") (class "Default")
      (node (ref "JP1") (pin "11") (pinfunction "RTCK_11") (pintype "passive"))
    )
    (net (code "62") (name "unconnected-(U1-A2-Pad3)") (class "Default")
      (node (ref "U1") (pin "3") (pinfunction "A2_3") (pintype "bidirectional"))
    )
    (net (code "63") (name "unconnected-(U1-A3-Pad4)") (class "Default")
      (node (ref "U1") (pin "4") (pinfunction "A3_4") (pintype "bidirectional"))
    )
    (net (code "64") (name "unconnected-(U1-A4-Pad5)") (class "Default")
      (node (ref "U1") (pin "5") (pinfunction "A4_5") (pintype "bidirectional"))
    )
    (net (code "65") (name "unconnected-(U1-A5-Pad6)") (class "Default")
      (node (ref "U1") (pin "6") (pinfunction "A5_6") (pintype "bidirectional"))
    )
    (net (code "66") (name "unconnected-(U1-A6-Pad7)") (class "Default")
      (node (ref "U1") (pin "7") (pinfunction "A6_7") (pintype "bidirectional"))
    )
    (net (code "67") (name "unconnected-(U1-A7-Pad8)") (class "Default")
      (node (ref "U1") (pin "8") (pinfunction "A7_8") (pintype "bidirectional"))
    )
    (net (code "68") (name "unconnected-(U1-A8-Pad9)") (class "Default")
      (node (ref "U1") (pin "9") (pinfunction "A8_9") (pintype "bidirectional"))
    )
    (net (code "69") (name "unconnected-(U1-B2-Pad17)") (class "Default")
      (node (ref "U1") (pin "17") (pinfunction "B2_17") (pintype "bidirectional"))
    )
    (net (code "70") (name "unconnected-(U1-B3-Pad16)") (class "Default")
      (node (ref "U1") (pin "16") (pinfunction "B3_16") (pintype "bidirectional"))
    )
    (net (code "71") (name "unconnected-(U1-B4-Pad15)") (class "Default")
      (node (ref "U1") (pin "15") (pinfunction "B4_15") (pintype "bidirectional"))
    )
    (net (code "72") (name "unconnected-(U1-B5-Pad14)") (class "Default")
      (node (ref "U1") (pin "14") (pinfunction "B5_14") (pintype "bidirectional"))
    )
    (net (code "73") (name "unconnected-(U1-B6-Pad13)") (class "Default")
      (node (ref "U1") (pin "13") (pinfunction "B6_13") (pintype "bidirectional"))
    )
    (net (code "74") (name "unconnected-(U1-B7-Pad12)") (class "Default")
      (node (ref "U1") (pin "12") (pinfunction "B7_12") (pintype "bidirectional"))
    )
    (net (code "75") (name "unconnected-(U1-B8-Pad11)") (class "Default")
      (node (ref "U1") (pin "11") (pinfunction "B8_11") (pintype "bidirectional"))
    )
    (net (code "76") (name "unconnected-(U2-PA8{slash}T1C1{slash}MCO-Pad29)") (class "Default")
      (node (ref "U2") (pin "29") (pinfunction "PA8/T1C1/MCO_29") (pintype "passive"))
    )
    (net (code "77") (name "unconnected-(U2-PB0{slash}ADC123_IN8{slash}T3C3{slash}T8C2N{slash}T1C2N-Pad18)") (class "Default")
      (node (ref "U2") (pin "18") (pinfunction "PB0/ADC123_IN8/T3C3/T8C2N/T1C2N_18") (pintype "passive"))
    )
    (net (code "78") (name "unconnected-(U2-PB1{slash}ADC123_IN9{slash}T3C4{slash}T8C3N{slash}T1C3N-Pad19)") (class "Default")
      (node (ref "U2") (pin "19") (pinfunction "PB1/ADC123_IN9/T3C4/T8C3N/T1C3N_19") (pintype "passive"))
    )
    (net (code "79") (name "unconnected-(U2-PB2{slash}BOOT1-Pad20)") (class "Default")
      (node (ref "U2") (pin "20") (pinfunction "PB2/BOOT1_20") (pintype "passive"))
    )
    (net (code "80") (name "unconnected-(U2-PB5{slash}I2C1_SMBA{slash}I2S3_SD{slash}SPI3_MOSI{slash}T3C2{slash}SPI1_MOSI-Pad41)") (class "Default")
      (node (ref "U2") (pin "41") (pinfunction "PB5/I2C1_SMBA/I2S3_SD/SPI3_MOSI/T3C2/SPI1_MOSI_41") (pintype "passive"))
    )
    (net (code "81") (name "unconnected-(U2-PB6{slash}I2C1_SCL{slash}T4C1{slash}USART1_Tx-Pad42)") (class "Default")
      (node (ref "U2") (pin "42") (pinfunction "PB6/I2C1_SCL/T4C1/USART1_Tx_42") (pintype "passive"))
    )
    (net (code "82") (name "unconnected-(U2-PB7{slash}I2C1_SDA{slash}FSMC_NADV{slash}USART1_Rx-Pad43)") (class "Default")
      (node (ref "U2") (pin "43") (pinfunction "PB7/I2C1_SDA/FSMC_NADV/USART1_Rx_43") (pintype "passive"))
    )
    (net (code "83") (name "unconnected-(U2-PB8{slash}SDIO_D4{slash}I2C1_SCL{slash}T4C3(7){slash}CAN_Rx-Pad45)") (class "Default")
      (node (ref "U2") (pin "45") (pinfunction "PB8/SDIO_D4/I2C1_SCL/T4C3(7)/CAN_Rx_45") (pintype "passive"))
    )
    (net (code "84") (name "unconnected-(U2-PB9{slash}SDIO_D5{slash}I2C1_SDA{slash}T4C4{slash}CAN_Tx-Pad46)") (class "Default")
      (node (ref "U2") (pin "46") (pinfunction "PB9/SDIO_D5/I2C1_SDA/T4C4/CAN_Tx_46") (pintype "passive"))
    )
    (net (code "85") (name "unconnected-(U2-PC14-OSC32_IN-Pad3)") (class "Default")
      (node (ref "U2") (pin "3") (pinfunction "PC14-OSC32_IN_3") (pintype "passive"))
    )
    (net (code "86") (name "unconnected-(U2-PC15-OSC32_OUT-Pad4)") (class "Default")
      (node (ref "U2") (pin "4") (pinfunction "PC15-OSC32_OUT_4") (pintype "passive"))
    )
  )
)
